# PMT_Protector_For_Optical_Stim_Gamma1a.net
KiCad netlist of a schematic drawn in EAGLE
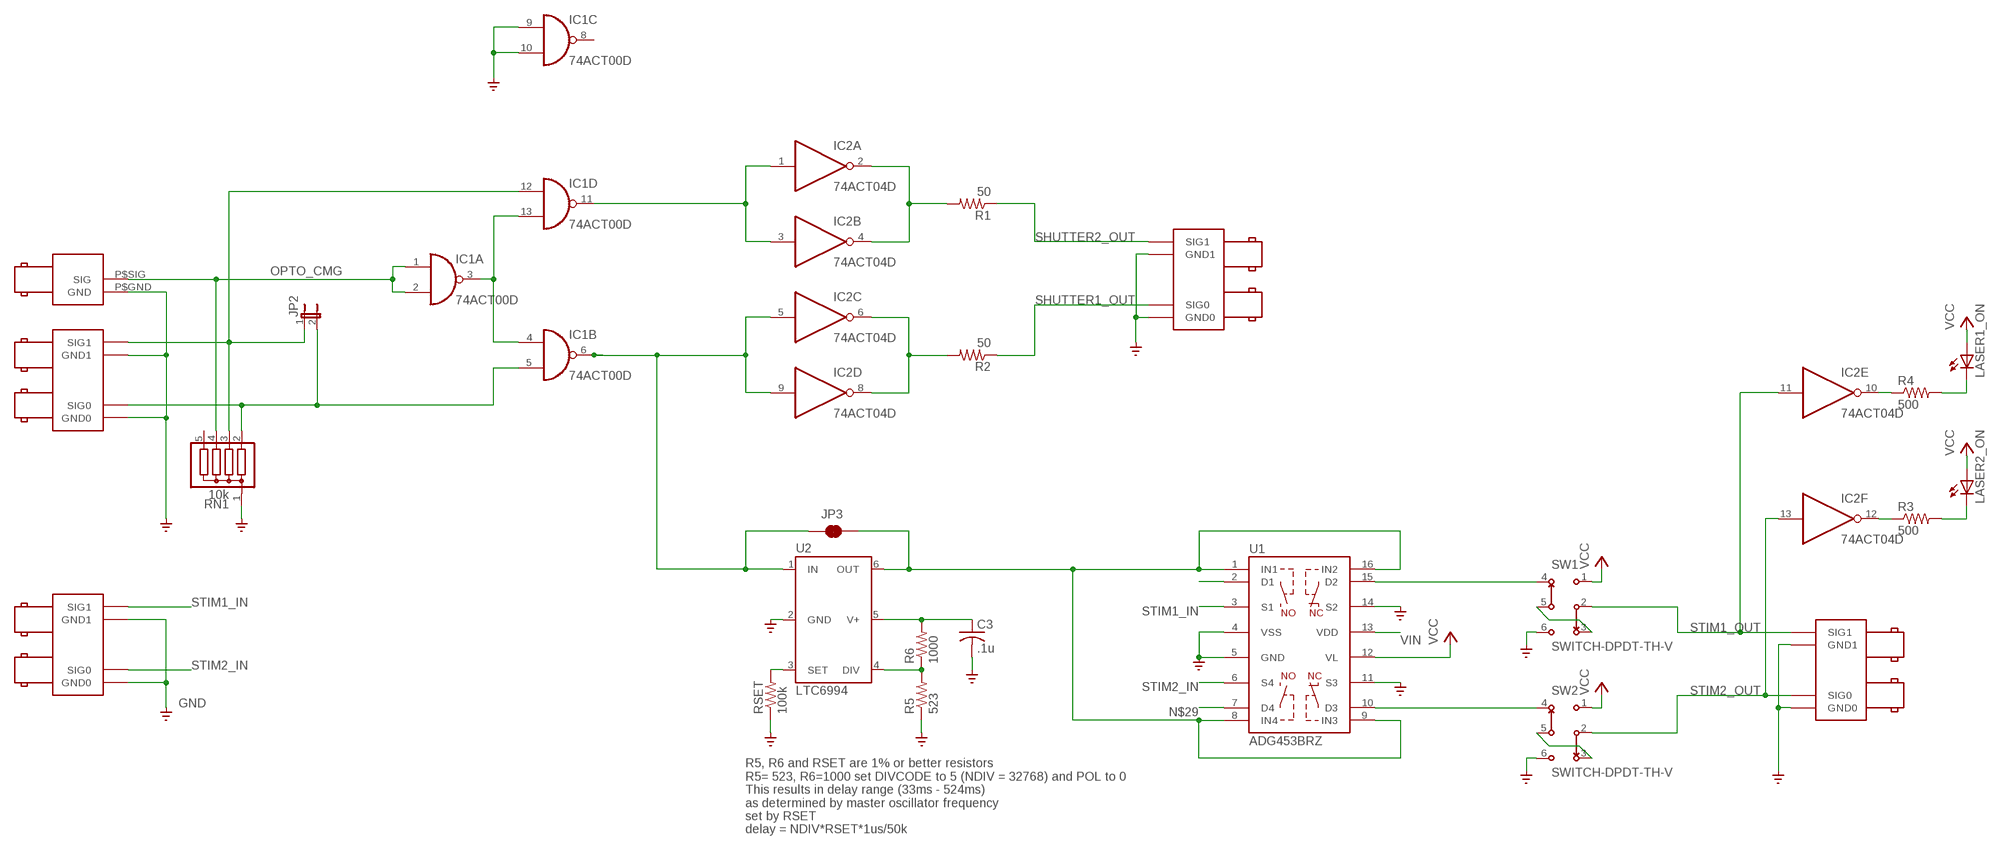
[diagram p0: schematic, sheet 1]
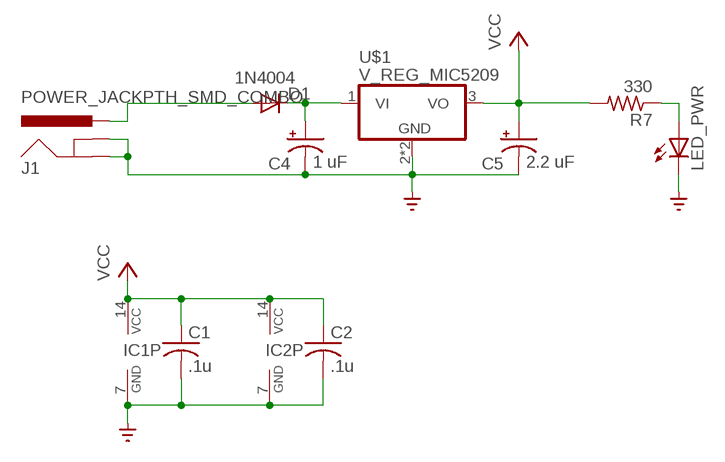
[diagram p1: schematic, sheet 2]

(export (version "E")
  (design (tool "Eeschema 10.0.6"))
  (components
    (comp (ref "C3")
      (value ".1u")
      (footprint "eagle-import:C0805K")
      (libsource (lib "eagle-import") (part "C-USC0805K"))
    )
    (comp (ref "IC1")
      (value "74ACT00D")
      (footprint "eagle-import:SO14")
      (libsource (lib "eagle-import") (part "7400DACT"))
    )
    (comp (ref "IC2")
      (value "74ACT04D")
      (footprint "eagle-import:SO14")
      (libsource (lib "eagle-import") (part "7404DACT"))
    )
    (comp (ref "JP2")
      (value "JP1E")
      (footprint "eagle-import:JP1")
      (libsource (lib "eagle-import") (part "JP1E"))
    )
    (comp (ref "JP3")
      (value "JUMPER-SMT_2_NC_TRACE_SILK")
      (footprint "eagle-import:SMT-JUMPER_2_NC_TRACE_SILK")
      (libsource (lib "eagle-import") (part "JUMPER-SMT_2_NC_TRACE_SILK"))
    )
    (comp (ref "LASER1_ON")
      (value "LED5MM")
      (footprint "eagle-import:LED5MM")
      (libsource (lib "eagle-import") (part "LED5MM"))
    )
    (comp (ref "LASER2_ON")
      (value "LED5MM")
      (footprint "eagle-import:LED5MM")
      (libsource (lib "eagle-import") (part "LED5MM"))
    )
    (comp (ref "OPTO_CMG")
      (value "BNC_RIGHT_ANGLE")
      (footprint "eagle-import:BNC_RIGHT_ANGLE")
      (libsource (lib "eagle-import") (part "BNC_RIGHT_ANGLE"))
    )
    (comp (ref "R1")
      (value "50")
      (footprint "eagle-import:R0805")
      (libsource (lib "eagle-import") (part "R-US_R0805"))
    )
    (comp (ref "R2")
      (value "50")
      (footprint "eagle-import:R0805")
      (libsource (lib "eagle-import") (part "R-US_R0805"))
    )
    (comp (ref "R3")
      (value "500")
      (footprint "eagle-import:R0805")
      (libsource (lib "eagle-import") (part "R-US_R0805"))
    )
    (comp (ref "R4")
      (value "500")
      (footprint "eagle-import:R0805")
      (libsource (lib "eagle-import") (part "R-US_R0805"))
    )
    (comp (ref "R5")
      (value "523")
      (footprint "eagle-import:R0805")
      (libsource (lib "eagle-import") (part "R-US_R0805"))
    )
    (comp (ref "R6")
      (value "1000")
      (footprint "eagle-import:R0805")
      (libsource (lib "eagle-import") (part "R-US_R0805"))
    )
    (comp (ref "RN1")
      (value "10k")
      (footprint "eagle-import:SIL5")
      (libsource (lib "eagle-import") (part "G04R"))
    )
    (comp (ref "RSET")
      (value "100k")
      (footprint "eagle-import:R0805")
      (libsource (lib "eagle-import") (part "R-US_R0805"))
    )
    (comp (ref "SHTR_IN")
      (value "BNC_RIGHT_ANGLE_DOUBLE")
      (footprint "eagle-import:BNC_RIGHT_ANGLE_DOUBLE")
      (libsource (lib "eagle-import") (part "BNC_RIGHT_ANGLE_DOUBLE"))
    )
    (comp (ref "SHTR_OUT")
      (value "BNC_RIGHT_ANGLE_DOUBLE")
      (footprint "eagle-import:BNC_RIGHT_ANGLE_DOUBLE")
      (libsource (lib "eagle-import") (part "BNC_RIGHT_ANGLE_DOUBLE"))
    )
    (comp (ref "STIM_IN")
      (value "BNC_RIGHT_ANGLE_DOUBLE")
      (footprint "eagle-import:BNC_RIGHT_ANGLE_DOUBLE")
      (libsource (lib "eagle-import") (part "BNC_RIGHT_ANGLE_DOUBLE"))
    )
    (comp (ref "STIM_OUT")
      (value "BNC_RIGHT_ANGLE_DOUBLE")
      (footprint "eagle-import:BNC_RIGHT_ANGLE_DOUBLE")
      (libsource (lib "eagle-import") (part "BNC_RIGHT_ANGLE_DOUBLE"))
    )
    (comp (ref "SW1")
      (value "SWITCH-DPDT-TH-V")
      (footprint "eagle-import:SWITCH-DPDT")
      (libsource (lib "eagle-import") (part "SWITCH-DPDT-TH-V"))
    )
    (comp (ref "SW2")
      (value "SWITCH-DPDT-TH-V")
      (footprint "eagle-import:SWITCH-DPDT")
      (libsource (lib "eagle-import") (part "SWITCH-DPDT-TH-V"))
    )
    (comp (ref "U1")
      (value "ADG453BRZ")
      (footprint "eagle-import:SO16")
      (libsource (lib "eagle-import") (part "ADG453?BRZ"))
    )
    (comp (ref "U2")
      (value "LTC6994")
      (footprint "eagle-import:SOT23-6")
      (libsource (lib "eagle-import") (part "TIMERBLOX_LTC6994SOT-23"))
    )
    (comp (ref "C1")
      (value ".1u")
      (footprint "eagle-import:C0805K")
      (libsource (lib "eagle-import") (part "C-USC0805K"))
    )
    (comp (ref "C2")
      (value ".1u")
      (footprint "eagle-import:C0805K")
      (libsource (lib "eagle-import") (part "C-USC0805K"))
    )
    (comp (ref "C4")
      (value "1 uF")
      (footprint "eagle-import:E2,5-5")
      (libsource (lib "eagle-import") (part "CPOL-USE2.5-5"))
    )
    (comp (ref "C5")
      (value "2.2 uF")
      (footprint "eagle-import:E2,5-5")
      (libsource (lib "eagle-import") (part "CPOL-USE2.5-5"))
    )
    (comp (ref "D1")
      (value "1N4004")
      (footprint "eagle-import:DO41-10")
      (libsource (lib "eagle-import") (part "1N4004"))
    )
    (comp (ref "J1")
      (value "POWER_JACKPTH_SMD_COMBO")
      (footprint "eagle-import:POWER_JACK_COMBO")
      (libsource (lib "eagle-import") (part "POWER_JACKPTH_SMD_COMBO"))
    )
    (comp (ref "LED_PWR")
      (value "LED5MM")
      (footprint "eagle-import:LED5MM")
      (libsource (lib "eagle-import") (part "LED5MM"))
    )
    (comp (ref "R7")
      (value "330")
      (footprint "eagle-import:R0805")
      (libsource (lib "eagle-import") (part "R-US_R0805"))
    )
    (comp (ref "U$1")
      (value "V_REG_MIC5209")
      (footprint "eagle-import:SOT-223")
      (libsource (lib "eagle-import") (part "V_REG_MIC5209"))
    )
  )
  (nets
    (net (code "1") (name "GND") (class "Default")
      (node (ref "C1") (pin "2") (pinfunction "2_2") (pintype "passive"))
      (node (ref "C2") (pin "2") (pinfunction "2_2") (pintype "passive"))
      (node (ref "C3") (pin "2") (pinfunction "2_2") (pintype "passive"))
      (node (ref "C4") (pin "-") (pinfunction "-_-") (pintype "passive"))
      (node (ref "C5") (pin "-") (pinfunction "-_-") (pintype "passive"))
      (node (ref "IC1") (pin "10") (pinfunction "I1_10") (pintype "input"))
      (node (ref "IC1") (pin "7") (pinfunction "GND_7") (pintype "power_in"))
      (node (ref "IC1") (pin "9") (pinfunction "I0_9") (pintype "input"))
      (node (ref "IC2") (pin "7") (pinfunction "GND_7") (pintype "power_in"))
      (node (ref "J1") (pin "GND") (pinfunction "GNDBREAK_GND") (pintype "bidirectional"))
      (node (ref "J1") (pin "GND@1") (pinfunction "GND_GND@1") (pintype "bidirectional"))
      (node (ref "LED_PWR") (pin "K") (pinfunction "C_K") (pintype "passive"))
      (node (ref "OPTO_CMG") (pin "P$GND") (pinfunction "GND_P$GND") (pintype "bidirectional"))
      (node (ref "R5") (pin "1") (pinfunction "1_1") (pintype "passive"))
      (node (ref "RN1") (pin "1") (pinfunction "1_1") (pintype "passive"))
      (node (ref "RSET") (pin "1") (pinfunction "1_1") (pintype "passive"))
      (node (ref "SHTR_IN") (pin "P$GND0") (pinfunction "GND0_P$GND0") (pintype "bidirectional"))
      (node (ref "SHTR_IN") (pin "P$GND1") (pinfunction "GND1_P$GND1") (pintype "bidirectional"))
      (node (ref "SHTR_OUT") (pin "P$GND0") (pinfunction "GND0_P$GND0") (pintype "bidirectional"))
      (node (ref "SHTR_OUT") (pin "P$GND1") (pinfunction "GND1_P$GND1") (pintype "bidirectional"))
      (node (ref "STIM_IN") (pin "P$GND0") (pinfunction "GND0_P$GND0") (pintype "bidirectional"))
      (node (ref "STIM_IN") (pin "P$GND1") (pinfunction "GND1_P$GND1") (pintype "bidirectional"))
      (node (ref "STIM_OUT") (pin "P$GND0") (pinfunction "GND0_P$GND0") (pintype "bidirectional"))
      (node (ref "STIM_OUT") (pin "P$GND1") (pinfunction "GND1_P$GND1") (pintype "bidirectional"))
      (node (ref "SW1") (pin "6") (pinfunction "6_6") (pintype "passive"))
      (node (ref "SW2") (pin "6") (pinfunction "6_6") (pintype "passive"))
      (node (ref "U$1") (pin "2") (pinfunction "GND_2") (pintype "passive"))
      (node (ref "U$1") (pin "4") (pinfunction "GND_4") (pintype "passive"))
      (node (ref "U1") (pin "11") (pinfunction "S3_11") (pintype "tri_state"))
      (node (ref "U1") (pin "14") (pinfunction "S2_14") (pintype "tri_state"))
      (node (ref "U1") (pin "4") (pinfunction "VSS_4") (pintype "power_in"))
      (node (ref "U1") (pin "5") (pinfunction "GND_5") (pintype "power_in"))
      (node (ref "U2") (pin "2") (pinfunction "GND_2") (pintype "bidirectional"))
    )
    (net (code "2") (name "N$29") (class "Default")
      (node (ref "SW2") (pin "4") (pinfunction "4_4") (pintype "passive"))
      (node (ref "U1") (pin "10") (pinfunction "D3_10") (pintype "tri_state"))
      (node (ref "U1") (pin "7") (pinfunction "D4_7") (pintype "tri_state"))
    )
    (net (code "3") (name "N$35") (class "Default")
      (node (ref "SW1") (pin "4") (pinfunction "4_4") (pintype "passive"))
      (node (ref "U1") (pin "15") (pinfunction "D2_15") (pintype "tri_state"))
      (node (ref "U1") (pin "2") (pinfunction "D1_2") (pintype "tri_state"))
    )
    (net (code "4") (name "Net-(IC1A-O)") (class "Default")
      (node (ref "IC1") (pin "13") (pinfunction "I1_13") (pintype "input"))
      (node (ref "IC1") (pin "3") (pinfunction "O_3") (pintype "output"))
      (node (ref "IC1") (pin "4") (pinfunction "I0_4") (pintype "input"))
    )
    (net (code "5") (name "Net-(IC1B-I1)") (class "Default")
      (node (ref "IC1") (pin "5") (pinfunction "I1_5") (pintype "input"))
      (node (ref "JP2") (pin "2") (pinfunction "2_2") (pintype "passive"))
      (node (ref "RN1") (pin "2") (pinfunction "2_2") (pintype "passive"))
      (node (ref "SHTR_IN") (pin "P$SIG0") (pinfunction "SIG0_P$SIG0") (pintype "bidirectional"))
    )
    (net (code "6") (name "Net-(IC1B-O)") (class "Default")
      (node (ref "IC1") (pin "6") (pinfunction "O_6") (pintype "output"))
      (node (ref "IC2") (pin "5") (pinfunction "I_5") (pintype "input"))
      (node (ref "IC2") (pin "9") (pinfunction "I_9") (pintype "input"))
      (node (ref "JP3") (pin "1") (pinfunction "1_1") (pintype "passive"))
      (node (ref "U2") (pin "1") (pinfunction "IN_1") (pintype "bidirectional"))
    )
    (net (code "7") (name "Net-(IC1D-I0)") (class "Default")
      (node (ref "IC1") (pin "12") (pinfunction "I0_12") (pintype "input"))
      (node (ref "JP2") (pin "1") (pinfunction "1_1") (pintype "passive"))
      (node (ref "RN1") (pin "3") (pinfunction "3_3") (pintype "passive"))
      (node (ref "SHTR_IN") (pin "P$SIG1") (pinfunction "SIG1_P$SIG1") (pintype "bidirectional"))
    )
    (net (code "8") (name "Net-(IC1D-O)") (class "Default")
      (node (ref "IC1") (pin "11") (pinfunction "O_11") (pintype "output"))
      (node (ref "IC2") (pin "1") (pinfunction "I_1") (pintype "input"))
      (node (ref "IC2") (pin "3") (pinfunction "I_3") (pintype "input"))
    )
    (net (code "9") (name "Net-(IC2A-O)") (class "Default")
      (node (ref "IC2") (pin "2") (pinfunction "O_2") (pintype "output"))
      (node (ref "IC2") (pin "4") (pinfunction "O_4") (pintype "output"))
      (node (ref "R1") (pin "2") (pinfunction "2_2") (pintype "passive"))
    )
    (net (code "10") (name "Net-(IC2C-O)") (class "Default")
      (node (ref "IC2") (pin "6") (pinfunction "O_6") (pintype "output"))
      (node (ref "IC2") (pin "8") (pinfunction "O_8") (pintype "output"))
      (node (ref "R2") (pin "2") (pinfunction "2_2") (pintype "passive"))
    )
    (net (code "11") (name "Net-(IC2E-O)") (class "Default")
      (node (ref "IC2") (pin "10") (pinfunction "O_10") (pintype "output"))
      (node (ref "R4") (pin "1") (pinfunction "1_1") (pintype "passive"))
    )
    (net (code "12") (name "Net-(IC2F-O)") (class "Default")
      (node (ref "IC2") (pin "12") (pinfunction "O_12") (pintype "output"))
      (node (ref "R3") (pin "1") (pinfunction "1_1") (pintype "passive"))
    )
    (net (code "13") (name "Net-(J1-PWR)") (class "Default")
      (node (ref "D1") (pin "A") (pinfunction "A_A") (pintype "passive"))
      (node (ref "J1") (pin "POWER") (pinfunction "PWR_POWER") (pintype "bidirectional"))
    )
    (net (code "14") (name "Net-(LASER1_ON-C)") (class "Default")
      (node (ref "LASER1_ON") (pin "K") (pinfunction "C_K") (pintype "passive"))
      (node (ref "R4") (pin "2") (pinfunction "2_2") (pintype "passive"))
    )
    (net (code "15") (name "Net-(LASER2_ON-C)") (class "Default")
      (node (ref "LASER2_ON") (pin "K") (pinfunction "C_K") (pintype "passive"))
      (node (ref "R3") (pin "2") (pinfunction "2_2") (pintype "passive"))
    )
    (net (code "16") (name "Net-(LED_PWR-PadA)") (class "Default")
      (node (ref "LED_PWR") (pin "A") (pinfunction "A_A") (pintype "passive"))
      (node (ref "R7") (pin "1") (pinfunction "1_1") (pintype "passive"))
    )
    (net (code "17") (name "Net-(SW1-Pad3)") (class "Default")
      (node (ref "SW1") (pin "3") (pinfunction "3_3") (pintype "passive"))
      (node (ref "SW1") (pin "5") (pinfunction "5_5") (pintype "passive"))
    )
    (net (code "18") (name "Net-(SW2-Pad3)") (class "Default")
      (node (ref "SW2") (pin "3") (pinfunction "3_3") (pintype "passive"))
      (node (ref "SW2") (pin "5") (pinfunction "5_5") (pintype "passive"))
    )
    (net (code "19") (name "Net-(U1-IN1)") (class "Default")
      (node (ref "JP3") (pin "2") (pinfunction "2_2") (pintype "passive"))
      (node (ref "U1") (pin "1") (pinfunction "IN1_1") (pintype "input"))
      (node (ref "U1") (pin "16") (pinfunction "IN2_16") (pintype "input"))
      (node (ref "U1") (pin "8") (pinfunction "IN4_8") (pintype "input"))
      (node (ref "U1") (pin "9") (pinfunction "IN3_9") (pintype "input"))
      (node (ref "U2") (pin "6") (pinfunction "OUT_6") (pintype "bidirectional"))
    )
    (net (code "20") (name "Net-(U2-DIV)") (class "Default")
      (node (ref "R5") (pin "2") (pinfunction "2_2") (pintype "passive"))
      (node (ref "R6") (pin "1") (pinfunction "1_1") (pintype "passive"))
      (node (ref "U2") (pin "4") (pinfunction "DIV_4") (pintype "bidirectional"))
    )
    (net (code "21") (name "Net-(U2-SET)") (class "Default")
      (node (ref "RSET") (pin "2") (pinfunction "2_2") (pintype "passive"))
      (node (ref "U2") (pin "3") (pinfunction "SET_3") (pintype "bidirectional"))
    )
    (net (code "22") (name "Net-(U2-V+)") (class "Default")
      (node (ref "C3") (pin "1") (pinfunction "1_1") (pintype "passive"))
      (node (ref "R6") (pin "2") (pinfunction "2_2") (pintype "passive"))
      (node (ref "U2") (pin "5") (pinfunction "V+_5") (pintype "bidirectional"))
    )
    (net (code "23") (name "OPTO_CMG") (class "Default")
      (node (ref "IC1") (pin "1") (pinfunction "I0_1") (pintype "input"))
      (node (ref "IC1") (pin "2") (pinfunction "I1_2") (pintype "input"))
      (node (ref "OPTO_CMG") (pin "P$SIG") (pinfunction "SIG_P$SIG") (pintype "bidirectional"))
      (node (ref "RN1") (pin "4") (pinfunction "4_4") (pintype "passive"))
    )
    (net (code "24") (name "SHUTTER1_OUT") (class "Default")
      (node (ref "R2") (pin "1") (pinfunction "1_1") (pintype "passive"))
      (node (ref "SHTR_OUT") (pin "P$SIG0") (pinfunction "SIG0_P$SIG0") (pintype "bidirectional"))
    )
    (net (code "25") (name "SHUTTER2_OUT") (class "Default")
      (node (ref "R1") (pin "1") (pinfunction "1_1") (pintype "passive"))
      (node (ref "SHTR_OUT") (pin "P$SIG1") (pinfunction "SIG1_P$SIG1") (pintype "bidirectional"))
    )
    (net (code "26") (name "STIM1_IN") (class "Default")
      (node (ref "STIM_IN") (pin "P$SIG1") (pinfunction "SIG1_P$SIG1") (pintype "bidirectional"))
      (node (ref "U1") (pin "3") (pinfunction "S1_3") (pintype "tri_state"))
    )
    (net (code "27") (name "STIM1_OUT") (class "Default")
      (node (ref "IC2") (pin "11") (pinfunction "I_11") (pintype "input"))
      (node (ref "STIM_OUT") (pin "P$SIG1") (pinfunction "SIG1_P$SIG1") (pintype "bidirectional"))
      (node (ref "SW1") (pin "2") (pinfunction "2_2") (pintype "passive"))
    )
    (net (code "28") (name "STIM2_IN") (class "Default")
      (node (ref "STIM_IN") (pin "P$SIG0") (pinfunction "SIG0_P$SIG0") (pintype "bidirectional"))
      (node (ref "U1") (pin "6") (pinfunction "S4_6") (pintype "tri_state"))
    )
    (net (code "29") (name "STIM2_OUT") (class "Default")
      (node (ref "IC2") (pin "13") (pinfunction "I_13") (pintype "input"))
      (node (ref "STIM_OUT") (pin "P$SIG0") (pinfunction "SIG0_P$SIG0") (pintype "bidirectional"))
      (node (ref "SW2") (pin "2") (pinfunction "2_2") (pintype "passive"))
    )
    (net (code "30") (name "VCC") (class "Default")
      (node (ref "C1") (pin "1") (pinfunction "1_1") (pintype "passive"))
      (node (ref "C2") (pin "1") (pinfunction "1_1") (pintype "passive"))
      (node (ref "C5") (pin "+") (pinfunction "+_+") (pintype "passive"))
      (node (ref "IC1") (pin "14") (pinfunction "VCC_14") (pintype "power_in"))
      (node (ref "IC2") (pin "14") (pinfunction "VCC_14") (pintype "power_in"))
      (node (ref "LASER1_ON") (pin "A") (pinfunction "A_A") (pintype "passive"))
      (node (ref "LASER2_ON") (pin "A") (pinfunction "A_A") (pintype "passive"))
      (node (ref "R7") (pin "2") (pinfunction "2_2") (pintype "passive"))
      (node (ref "SW1") (pin "1") (pinfunction "1_1") (pintype "passive"))
      (node (ref "SW2") (pin "1") (pinfunction "1_1") (pintype "passive"))
      (node (ref "U$1") (pin "3") (pinfunction "VO_3") (pintype "passive"))
      (node (ref "U1") (pin "12") (pinfunction "VL_12") (pintype "power_in"))
    )
    (net (code "31") (name "VIN") (class "Default")
      (node (ref "C4") (pin "+") (pinfunction "+_+") (pintype "passive"))
      (node (ref "D1") (pin "C") (pinfunction "C_C") (pintype "passive"))
      (node (ref "U$1") (pin "1") (pinfunction "VI_1") (pintype "input"))
      (node (ref "U1") (pin "13") (pinfunction "VDD_13") (pintype "power_in"))
    )
    (net (code "32") (name "unconnected-(IC1C-O-Pad8)") (class "Default")
      (node (ref "IC1") (pin "8") (pinfunction "O_8") (pintype "output"))
    )
    (net (code "33") (name "unconnected-(RN1-Pad5)") (class "Default")
      (node (ref "RN1") (pin "5") (pinfunction "5_5") (pintype "passive"))
    )
  )
)
